# ESC_C.net
KiCad netlist of a schematic drawn in Altium Designer
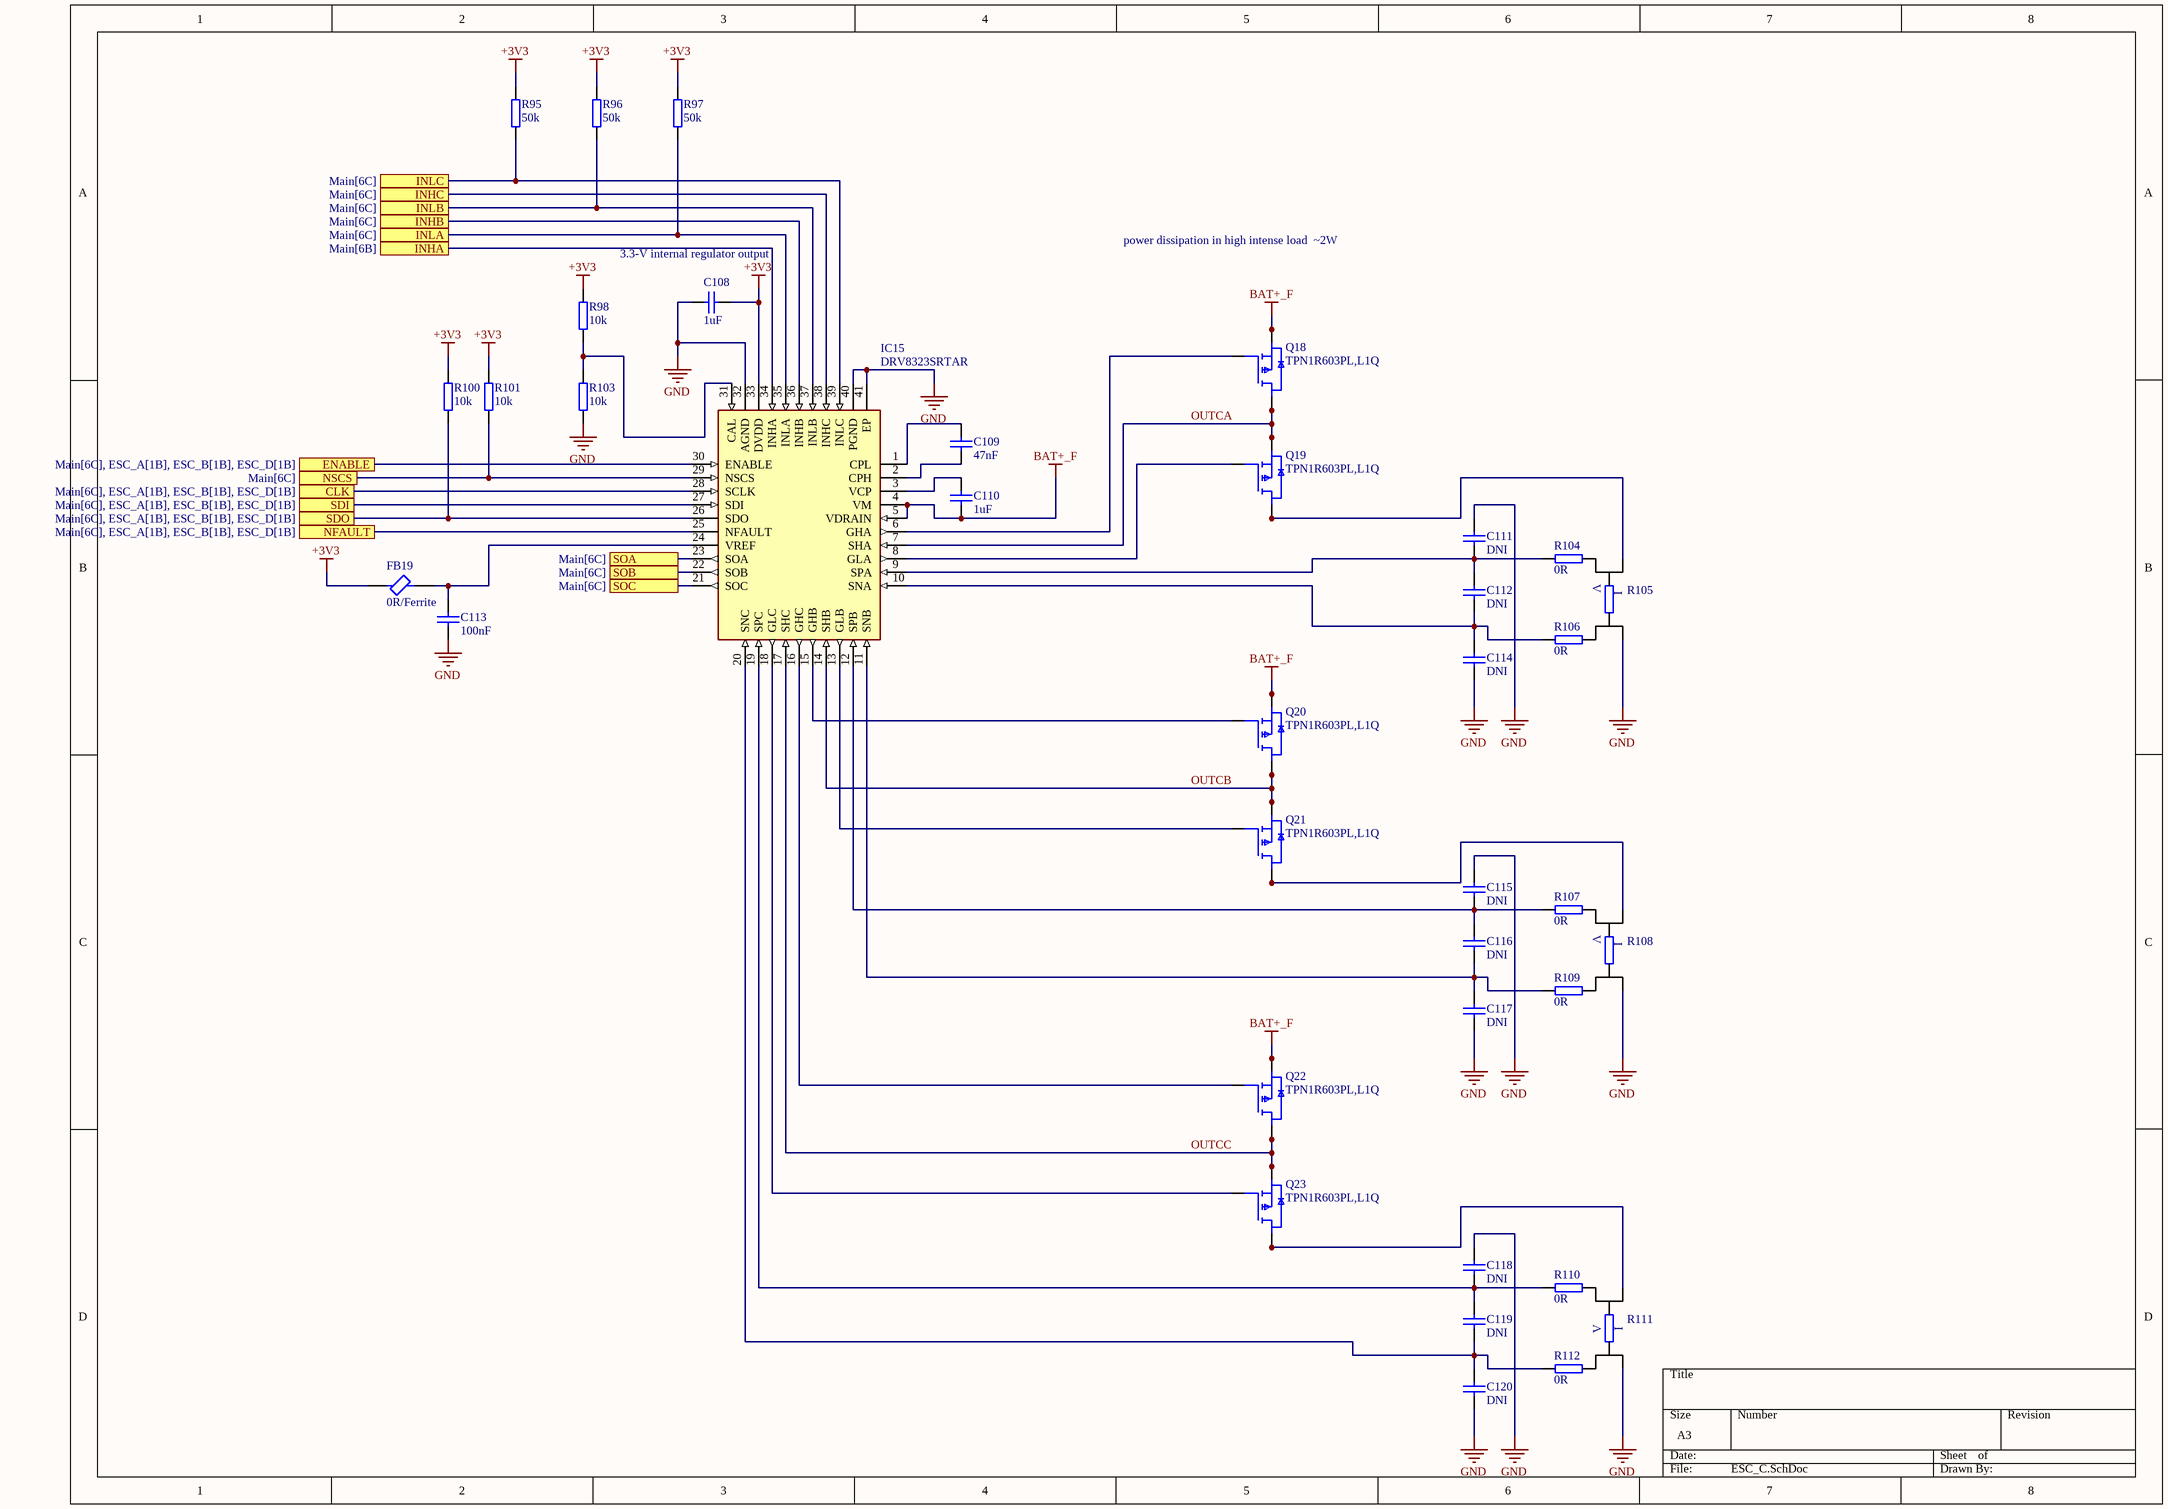
[diagram p0: ESC_C.SchDoc]

(export (version "E")
  (design (tool "Eeschema 10.0.6"))
  (components
    (comp (ref "C108")
      (value "1uF")
      (footprint "CAP0402")
      (fields (field (name "VOLTAGE") "val") (field (name "Comment") "Cap0402"))
      (libsource (lib "capacitorsSMD") (part "Cap0402"))
    )
    (comp (ref "C109")
      (value "47nF")
      (footprint "CAP0603")
      (description "50V")
      (fields (field (name "Comment") "CapSMD0603") (field (name "PUBLISHER") "Altium Limited"))
      (libsource (lib "capacitorsSMD") (part "CapSMD0603"))
    )
    (comp (ref "C110")
      (value "1uF")
      (footprint "CAP0603")
      (description "50V")
      (fields (field (name "Comment") "CapSMD0603") (field (name "PUBLISHER") "Altium Limited"))
      (libsource (lib "capacitorsSMD") (part "CapSMD0603"))
    )
    (comp (ref "C111")
      (value "DNI")
      (footprint "CAP0402")
      (fields (field (name "Comment") "Cap0402"))
      (libsource (lib "capacitorsSMD") (part "Cap0402"))
    )
    (comp (ref "C112")
      (value "DNI")
      (footprint "CAP0402")
      (fields (field (name "Comment") "Cap0402"))
      (libsource (lib "capacitorsSMD") (part "Cap0402"))
    )
    (comp (ref "C113")
      (value "100nF")
      (footprint "CAP0402")
      (fields (field (name "VOLTAGE") "6V3") (field (name "Comment") "Cap0402"))
      (libsource (lib "capacitorsSMD") (part "Cap0402"))
    )
    (comp (ref "C114")
      (value "DNI")
      (footprint "CAP0402")
      (fields (field (name "Comment") "Cap0402"))
      (libsource (lib "capacitorsSMD") (part "Cap0402"))
    )
    (comp (ref "C115")
      (value "DNI")
      (footprint "CAP0402")
      (fields (field (name "Comment") "Cap0402"))
      (libsource (lib "capacitorsSMD") (part "Cap0402"))
    )
    (comp (ref "C116")
      (value "DNI")
      (footprint "CAP0402")
      (fields (field (name "Comment") "Cap0402"))
      (libsource (lib "capacitorsSMD") (part "Cap0402"))
    )
    (comp (ref "C117")
      (value "DNI")
      (footprint "CAP0402")
      (fields (field (name "Comment") "Cap0402"))
      (libsource (lib "capacitorsSMD") (part "Cap0402"))
    )
    (comp (ref "C118")
      (value "DNI")
      (footprint "CAP0402")
      (fields (field (name "Comment") "Cap0402"))
      (libsource (lib "capacitorsSMD") (part "Cap0402"))
    )
    (comp (ref "C119")
      (value "DNI")
      (footprint "CAP0402")
      (fields (field (name "Comment") "Cap0402"))
      (libsource (lib "capacitorsSMD") (part "Cap0402"))
    )
    (comp (ref "C120")
      (value "DNI")
      (footprint "CAP0402")
      (fields (field (name "Comment") "Cap0402"))
      (libsource (lib "capacitorsSMD") (part "Cap0402"))
    )
    (comp (ref "FB19")
      (value "0R/Ferrite")
      (footprint "SamacSys:NFZ15SG152SN10B")
      (description "Ferrite Bead")
      (fields
        (field (name "MANUFACTURER_PART_NUMBER") "BLM15PE471SH1D")
        (field (name "MOUSER PART NUMBER") "81-BLM15PE471SH1D")
      )
      (libsource (lib "SamacSys") (part "BLM15PE471SH1D"))
    )
    (comp (ref "IC15")
      (value "DRV8323SRTAR")
      (footprint "SamacSys:QFN50P600X600X80-41N-D")
      (description "Integrated Circuit")
      (fields (field (name "MOUSER PART NUMBER") "595-DRV8323SRTAR"))
      (libsource (lib "*") (part "DRV8323SRTAR"))
    )
    (comp (ref "Q18")
      (value "TPN1R603PL,L1Q")
      (footprint "SamacSys:TPN1R603PLL1Q")
      (description "MOSFET (N-Channel)")
      (fields (field (name "MOUSER PART NUMBER") "757-TPN1R603PLL1Q"))
      (libsource (lib "SamacSys") (part "TPN1R603PL,L1Q"))
    )
    (comp (ref "Q19")
      (value "TPN1R603PL,L1Q")
      (footprint "SamacSys:TPN1R603PLL1Q")
      (description "MOSFET (N-Channel)")
      (fields (field (name "MOUSER PART NUMBER") "757-TPN1R603PLL1Q"))
      (libsource (lib "SamacSys") (part "TPN1R603PL,L1Q"))
    )
    (comp (ref "Q20")
      (value "TPN1R603PL,L1Q")
      (footprint "SamacSys:TPN1R603PLL1Q")
      (description "MOSFET (N-Channel)")
      (fields (field (name "MOUSER PART NUMBER") "757-TPN1R603PLL1Q"))
      (libsource (lib "SamacSys") (part "TPN1R603PL,L1Q"))
    )
    (comp (ref "Q21")
      (value "TPN1R603PL,L1Q")
      (footprint "SamacSys:TPN1R603PLL1Q")
      (description "MOSFET (N-Channel)")
      (fields (field (name "MOUSER PART NUMBER") "757-TPN1R603PLL1Q"))
      (libsource (lib "SamacSys") (part "TPN1R603PL,L1Q"))
    )
    (comp (ref "Q22")
      (value "TPN1R603PL,L1Q")
      (footprint "SamacSys:TPN1R603PLL1Q")
      (description "MOSFET (N-Channel)")
      (fields (field (name "MOUSER PART NUMBER") "757-TPN1R603PLL1Q"))
      (libsource (lib "SamacSys") (part "TPN1R603PL,L1Q"))
    )
    (comp (ref "Q23")
      (value "TPN1R603PL,L1Q")
      (footprint "SamacSys:TPN1R603PLL1Q")
      (description "MOSFET (N-Channel)")
      (fields (field (name "MOUSER PART NUMBER") "757-TPN1R603PLL1Q"))
      (libsource (lib "SamacSys") (part "TPN1R603PL,L1Q"))
    )
    (comp (ref "R95")
      (value "50k")
      (footprint "RES0402")
      (fields (field (name "Comment") "Res0402"))
      (libsource (lib "resistorSMD") (part "Res0402"))
    )
    (comp (ref "R96")
      (value "50k")
      (footprint "RES0402")
      (fields (field (name "Comment") "Res0402"))
      (libsource (lib "resistorSMD") (part "Res0402"))
    )
    (comp (ref "R97")
      (value "50k")
      (footprint "RES0402")
      (fields (field (name "Comment") "Res0402"))
      (libsource (lib "resistorSMD") (part "Res0402"))
    )
    (comp (ref "R98")
      (value "10k")
      (footprint "RES0402")
      (fields (field (name "Comment") "Res0402"))
      (libsource (lib "resistorSMD") (part "Res0402"))
    )
    (comp (ref "R100")
      (value "10k")
      (footprint "RES0402")
      (fields (field (name "Comment") "Res0402"))
      (libsource (lib "resistorSMD") (part "Res0402"))
    )
    (comp (ref "R101")
      (value "10k")
      (footprint "RES0402")
      (fields (field (name "Comment") "Res0402"))
      (libsource (lib "resistorSMD") (part "Res0402"))
    )
    (comp (ref "R103")
      (value "10k")
      (footprint "RES0402")
      (fields (field (name "Comment") "Res0402"))
      (libsource (lib "resistorSMD") (part "Res0402"))
    )
    (comp (ref "R104")
      (value "0R")
      (footprint "RES0402")
      (fields (field (name "Comment") "Res0402"))
      (libsource (lib "resistorSMD") (part "Res0402"))
    )
    (comp (ref "R105")
      (value "WSK12161L000FEA")
      (footprint "SamacSys:WSK12161L000FEA")
      (description "Resistor")
      (fields
        (field (name "MANUFACTURER_PART_NUMBER") "WSK1216L5000FEA")
        (field (name "MOUSER PART NUMBER") "71-WSK1216L5000FEA")
      )
      (libsource (lib "SamacSys") (part "WSK1216L5000FEA"))
    )
    (comp (ref "R106")
      (value "0R")
      (footprint "RES0402")
      (fields (field (name "Comment") "Res0402"))
      (libsource (lib "resistorSMD") (part "Res0402"))
    )
    (comp (ref "R107")
      (value "0R")
      (footprint "RES0402")
      (fields (field (name "Comment") "Res0402"))
      (libsource (lib "resistorSMD") (part "Res0402"))
    )
    (comp (ref "R108")
      (value "WSK12161L000FEA")
      (footprint "SamacSys:WSK12161L000FEA")
      (description "Resistor")
      (fields
        (field (name "MANUFACTURER_PART_NUMBER") "WSK1216L5000FEA")
        (field (name "MOUSER PART NUMBER") "71-WSK1216L5000FEA")
      )
      (libsource (lib "SamacSys") (part "WSK1216L5000FEA"))
    )
    (comp (ref "R109")
      (value "0R")
      (footprint "RES0402")
      (fields (field (name "Comment") "Res0402"))
      (libsource (lib "resistorSMD") (part "Res0402"))
    )
    (comp (ref "R110")
      (value "0R")
      (footprint "RES0402")
      (fields (field (name "Comment") "Res0402"))
      (libsource (lib "resistorSMD") (part "Res0402"))
    )
    (comp (ref "R111")
      (value "WSK12161L000FEA")
      (footprint "SamacSys:WSK12161L000FEA")
      (description "Resistor")
      (fields
        (field (name "MANUFACTURER_PART_NUMBER") "WSK1216L5000FEA")
        (field (name "MOUSER PART NUMBER") "71-WSK1216L5000FEA")
      )
      (libsource (lib "SamacSys") (part "WSK1216L5000FEA"))
    )
    (comp (ref "R112")
      (value "0R")
      (footprint "RES0402")
      (fields (field (name "Comment") "Res0402"))
      (libsource (lib "resistorSMD") (part "Res0402"))
    )
  )
  (nets
    (net (code "1") (name "+3V3") (class "Default")
      (node (ref "C108") (pin "2") (pinfunction "2_2") (pintype "passive"))
      (node (ref "FB19") (pin "1") (pinfunction "1_1") (pintype "passive"))
      (node (ref "IC15") (pin "33") (pinfunction "DVDD_33") (pintype "power_in"))
      (node (ref "R100") (pin "2") (pinfunction "2_2") (pintype "passive"))
      (node (ref "R101") (pin "2") (pinfunction "2_2") (pintype "passive"))
      (node (ref "R95") (pin "2") (pinfunction "2_2") (pintype "passive"))
      (node (ref "R96") (pin "2") (pinfunction "2_2") (pintype "passive"))
      (node (ref "R97") (pin "2") (pinfunction "2_2") (pintype "passive"))
      (node (ref "R98") (pin "2") (pinfunction "2_2") (pintype "passive"))
    )
    (net (code "2") (name "/CLK") (class "Default")
      (node (ref "IC15") (pin "28") (pinfunction "SCLK_28") (pintype "input"))
    )
    (net (code "3") (name "/ENABLE") (class "Default")
      (node (ref "IC15") (pin "30") (pinfunction "ENABLE_30") (pintype "input"))
    )
    (net (code "4") (name "/INHA") (class "Default")
      (node (ref "IC15") (pin "34") (pinfunction "INHA_34") (pintype "input"))
    )
    (net (code "5") (name "/INHB") (class "Default")
      (node (ref "IC15") (pin "36") (pinfunction "INHB_36") (pintype "input"))
    )
    (net (code "6") (name "/INHC") (class "Default")
      (node (ref "IC15") (pin "38") (pinfunction "INHC_38") (pintype "input"))
    )
    (net (code "7") (name "/INLA") (class "Default")
      (node (ref "IC15") (pin "35") (pinfunction "INLA_35") (pintype "input"))
      (node (ref "R97") (pin "1") (pinfunction "1_1") (pintype "passive"))
    )
    (net (code "8") (name "/INLB") (class "Default")
      (node (ref "IC15") (pin "37") (pinfunction "INLB_37") (pintype "input"))
      (node (ref "R96") (pin "1") (pinfunction "1_1") (pintype "passive"))
    )
    (net (code "9") (name "/INLC") (class "Default")
      (node (ref "IC15") (pin "39") (pinfunction "INLC_39") (pintype "input"))
      (node (ref "R95") (pin "1") (pinfunction "1_1") (pintype "passive"))
    )
    (net (code "10") (name "/NFAULT") (class "Default")
      (node (ref "IC15") (pin "25") (pinfunction "NFAULT_25") (pintype "passive"))
    )
    (net (code "11") (name "/NSCS") (class "Default")
      (node (ref "IC15") (pin "29") (pinfunction "NSCS_29") (pintype "input"))
      (node (ref "R101") (pin "1") (pinfunction "1_1") (pintype "passive"))
    )
    (net (code "12") (name "/OUTCA") (class "Default")
      (node (ref "IC15") (pin "7") (pinfunction "SHA_7") (pintype "input"))
      (node (ref "Q18") (pin "5") (pinfunction "D_1_5") (pintype "passive"))
      (node (ref "Q18") (pin "6") (pinfunction "D_2_6") (pintype "passive"))
      (node (ref "Q18") (pin "7") (pinfunction "D_3_7") (pintype "passive"))
      (node (ref "Q18") (pin "8") (pinfunction "D_4_8") (pintype "passive"))
      (node (ref "Q18") (pin "9") (pinfunction "D_4_9") (pintype "passive"))
      (node (ref "Q19") (pin "1") (pinfunction "S_1_1") (pintype "passive"))
      (node (ref "Q19") (pin "2") (pinfunction "S_2_2") (pintype "passive"))
      (node (ref "Q19") (pin "3") (pinfunction "S_3_3") (pintype "passive"))
    )
    (net (code "13") (name "/OUTCB") (class "Default")
      (node (ref "IC15") (pin "14") (pinfunction "SHB_14") (pintype "input"))
      (node (ref "Q20") (pin "5") (pinfunction "D_1_5") (pintype "passive"))
      (node (ref "Q20") (pin "6") (pinfunction "D_2_6") (pintype "passive"))
      (node (ref "Q20") (pin "7") (pinfunction "D_3_7") (pintype "passive"))
      (node (ref "Q20") (pin "8") (pinfunction "D_4_8") (pintype "passive"))
      (node (ref "Q20") (pin "9") (pinfunction "D_4_9") (pintype "passive"))
      (node (ref "Q21") (pin "1") (pinfunction "S_1_1") (pintype "passive"))
      (node (ref "Q21") (pin "2") (pinfunction "S_2_2") (pintype "passive"))
      (node (ref "Q21") (pin "3") (pinfunction "S_3_3") (pintype "passive"))
    )
    (net (code "14") (name "/OUTCC") (class "Default")
      (node (ref "IC15") (pin "17") (pinfunction "SHC_17") (pintype "input"))
      (node (ref "Q22") (pin "5") (pinfunction "D_1_5") (pintype "passive"))
      (node (ref "Q22") (pin "6") (pinfunction "D_2_6") (pintype "passive"))
      (node (ref "Q22") (pin "7") (pinfunction "D_3_7") (pintype "passive"))
      (node (ref "Q22") (pin "8") (pinfunction "D_4_8") (pintype "passive"))
      (node (ref "Q22") (pin "9") (pinfunction "D_4_9") (pintype "passive"))
      (node (ref "Q23") (pin "1") (pinfunction "S_1_1") (pintype "passive"))
      (node (ref "Q23") (pin "2") (pinfunction "S_2_2") (pintype "passive"))
      (node (ref "Q23") (pin "3") (pinfunction "S_3_3") (pintype "passive"))
    )
    (net (code "15") (name "/SDI") (class "Default")
      (node (ref "IC15") (pin "27") (pinfunction "SDI_27") (pintype "input"))
    )
    (net (code "16") (name "/SDO") (class "Default")
      (node (ref "IC15") (pin "26") (pinfunction "SDO_26") (pintype "passive"))
      (node (ref "R100") (pin "1") (pinfunction "1_1") (pintype "passive"))
    )
    (net (code "17") (name "/SOA") (class "Default")
      (node (ref "IC15") (pin "23") (pinfunction "SOA_23") (pintype "output"))
    )
    (net (code "18") (name "/SOB") (class "Default")
      (node (ref "IC15") (pin "22") (pinfunction "SOB_22") (pintype "output"))
    )
    (net (code "19") (name "/SOC") (class "Default")
      (node (ref "IC15") (pin "21") (pinfunction "SOC_21") (pintype "output"))
    )
    (net (code "20") (name "BAT+_F") (class "Default")
      (node (ref "C110") (pin "1") (pinfunction "1_1") (pintype "passive"))
      (node (ref "IC15") (pin "4") (pinfunction "VM_4") (pintype "power_in"))
      (node (ref "IC15") (pin "5") (pinfunction "VDRAIN_5") (pintype "input"))
      (node (ref "Q18") (pin "1") (pinfunction "S_1_1") (pintype "passive"))
      (node (ref "Q18") (pin "2") (pinfunction "S_2_2") (pintype "passive"))
      (node (ref "Q18") (pin "3") (pinfunction "S_3_3") (pintype "passive"))
      (node (ref "Q20") (pin "1") (pinfunction "S_1_1") (pintype "passive"))
      (node (ref "Q20") (pin "2") (pinfunction "S_2_2") (pintype "passive"))
      (node (ref "Q20") (pin "3") (pinfunction "S_3_3") (pintype "passive"))
      (node (ref "Q22") (pin "1") (pinfunction "S_1_1") (pintype "passive"))
      (node (ref "Q22") (pin "2") (pinfunction "S_2_2") (pintype "passive"))
      (node (ref "Q22") (pin "3") (pinfunction "S_3_3") (pintype "passive"))
    )
    (net (code "21") (name "GND") (class "Default")
      (node (ref "C108") (pin "1") (pinfunction "1_1") (pintype "passive"))
      (node (ref "C111") (pin "1") (pinfunction "1_1") (pintype "passive"))
      (node (ref "C113") (pin "1") (pinfunction "1_1") (pintype "passive"))
      (node (ref "C114") (pin "2") (pinfunction "2_2") (pintype "passive"))
      (node (ref "C115") (pin "1") (pinfunction "1_1") (pintype "passive"))
      (node (ref "C117") (pin "2") (pinfunction "2_2") (pintype "passive"))
      (node (ref "C118") (pin "1") (pinfunction "1_1") (pintype "passive"))
      (node (ref "C120") (pin "2") (pinfunction "2_2") (pintype "passive"))
      (node (ref "IC15") (pin "32") (pinfunction "AGND_32") (pintype "power_in"))
      (node (ref "IC15") (pin "40") (pinfunction "PGND_40") (pintype "power_in"))
      (node (ref "IC15") (pin "41") (pinfunction "EP_41") (pintype "power_in"))
      (node (ref "R103") (pin "1") (pinfunction "1_1") (pintype "passive"))
      (node (ref "R105") (pin "4") (pinfunction "4_4") (pintype "passive"))
      (node (ref "R108") (pin "4") (pinfunction "4_4") (pintype "passive"))
      (node (ref "R111") (pin "1") (pinfunction "1_1") (pintype "passive"))
    )
    (net (code "22") (name "Net-(IC15-CAL)") (class "Default")
      (node (ref "IC15") (pin "31") (pinfunction "CAL_31") (pintype "input"))
      (node (ref "R103") (pin "2") (pinfunction "2_2") (pintype "passive"))
      (node (ref "R98") (pin "1") (pinfunction "1_1") (pintype "passive"))
    )
    (net (code "23") (name "Net-(IC15-CPH)") (class "Default")
      (node (ref "C109") (pin "1") (pinfunction "1_1") (pintype "passive"))
      (node (ref "IC15") (pin "2") (pinfunction "CPH_2") (pintype "power_in"))
    )
    (net (code "24") (name "Net-(IC15-CPL)") (class "Default")
      (node (ref "C109") (pin "2") (pinfunction "2_2") (pintype "passive"))
      (node (ref "IC15") (pin "1") (pinfunction "CPL_1") (pintype "power_in"))
    )
    (net (code "25") (name "Net-(IC15-GHA)") (class "Default")
      (node (ref "IC15") (pin "6") (pinfunction "GHA_6") (pintype "output"))
      (node (ref "Q18") (pin "4") (pinfunction "G_4") (pintype "passive"))
    )
    (net (code "26") (name "Net-(IC15-GHB)") (class "Default")
      (node (ref "IC15") (pin "15") (pinfunction "GHB_15") (pintype "output"))
      (node (ref "Q20") (pin "4") (pinfunction "G_4") (pintype "passive"))
    )
    (net (code "27") (name "Net-(IC15-GHC)") (class "Default")
      (node (ref "IC15") (pin "16") (pinfunction "GHC_16") (pintype "output"))
      (node (ref "Q22") (pin "4") (pinfunction "G_4") (pintype "passive"))
    )
    (net (code "28") (name "Net-(IC15-GLA)") (class "Default")
      (node (ref "IC15") (pin "8") (pinfunction "GLA_8") (pintype "output"))
      (node (ref "Q19") (pin "4") (pinfunction "G_4") (pintype "passive"))
    )
    (net (code "29") (name "Net-(IC15-GLB)") (class "Default")
      (node (ref "IC15") (pin "13") (pinfunction "GLB_13") (pintype "output"))
      (node (ref "Q21") (pin "4") (pinfunction "G_4") (pintype "passive"))
    )
    (net (code "30") (name "Net-(IC15-GLC)") (class "Default")
      (node (ref "IC15") (pin "18") (pinfunction "GLC_18") (pintype "output"))
      (node (ref "Q23") (pin "4") (pinfunction "G_4") (pintype "passive"))
    )
    (net (code "31") (name "Net-(IC15-SNA)") (class "Default")
      (node (ref "C112") (pin "2") (pinfunction "2_2") (pintype "passive"))
      (node (ref "C114") (pin "1") (pinfunction "1_1") (pintype "passive"))
      (node (ref "IC15") (pin "10") (pinfunction "SNA_10") (pintype "input"))
      (node (ref "R106") (pin "1") (pinfunction "1_1") (pintype "passive"))
    )
    (net (code "32") (name "Net-(IC15-SNB)") (class "Default")
      (node (ref "C116") (pin "2") (pinfunction "2_2") (pintype "passive"))
      (node (ref "C117") (pin "1") (pinfunction "1_1") (pintype "passive"))
      (node (ref "IC15") (pin "11") (pinfunction "SNB_11") (pintype "input"))
      (node (ref "R109") (pin "1") (pinfunction "1_1") (pintype "passive"))
    )
    (net (code "33") (name "Net-(IC15-SNC)") (class "Default")
      (node (ref "C119") (pin "2") (pinfunction "2_2") (pintype "passive"))
      (node (ref "C120") (pin "1") (pinfunction "1_1") (pintype "passive"))
      (node (ref "IC15") (pin "20") (pinfunction "SNC_20") (pintype "input"))
      (node (ref "R112") (pin "1") (pinfunction "1_1") (pintype "passive"))
    )
    (net (code "34") (name "Net-(IC15-SPA)") (class "Default")
      (node (ref "C111") (pin "2") (pinfunction "2_2") (pintype "passive"))
      (node (ref "C112") (pin "1") (pinfunction "1_1") (pintype "passive"))
      (node (ref "IC15") (pin "9") (pinfunction "SPA_9") (pintype "input"))
      (node (ref "R104") (pin "1") (pinfunction "1_1") (pintype "passive"))
    )
    (net (code "35") (name "Net-(IC15-SPB)") (class "Default")
      (node (ref "C115") (pin "2") (pinfunction "2_2") (pintype "passive"))
      (node (ref "C116") (pin "1") (pinfunction "1_1") (pintype "passive"))
      (node (ref "IC15") (pin "12") (pinfunction "SPB_12") (pintype "input"))
      (node (ref "R107") (pin "1") (pinfunction "1_1") (pintype "passive"))
    )
    (net (code "36") (name "Net-(IC15-SPC)") (class "Default")
      (node (ref "C118") (pin "2") (pinfunction "2_2") (pintype "passive"))
      (node (ref "C119") (pin "1") (pinfunction "1_1") (pintype "passive"))
      (node (ref "IC15") (pin "19") (pinfunction "SPC_19") (pintype "input"))
      (node (ref "R110") (pin "1") (pinfunction "1_1") (pintype "passive"))
    )
    (net (code "37") (name "Net-(IC15-VCP)") (class "Default")
      (node (ref "C110") (pin "2") (pinfunction "2_2") (pintype "passive"))
      (node (ref "IC15") (pin "3") (pinfunction "VCP_3") (pintype "power_in"))
    )
    (net (code "38") (name "Net-(IC15-VREF)") (class "Default")
      (node (ref "C113") (pin "2") (pinfunction "2_2") (pintype "passive"))
      (node (ref "FB19") (pin "2") (pinfunction "2_2") (pintype "passive"))
      (node (ref "IC15") (pin "24") (pinfunction "VREF_24") (pintype "power_in"))
    )
    (net (code "39") (name "Net-(Q19-D_1)") (class "Default")
      (node (ref "Q19") (pin "5") (pinfunction "D_1_5") (pintype "passive"))
      (node (ref "Q19") (pin "6") (pinfunction "D_2_6") (pintype "passive"))
      (node (ref "Q19") (pin "7") (pinfunction "D_3_7") (pintype "passive"))
      (node (ref "Q19") (pin "8") (pinfunction "D_4_8") (pintype "passive"))
      (node (ref "Q19") (pin "9") (pinfunction "D_4_9") (pintype "passive"))
      (node (ref "R105") (pin "1") (pinfunction "1_1") (pintype "passive"))
    )
    (net (code "40") (name "Net-(Q21-D_1)") (class "Default")
      (node (ref "Q21") (pin "5") (pinfunction "D_1_5") (pintype "passive"))
      (node (ref "Q21") (pin "6") (pinfunction "D_2_6") (pintype "passive"))
      (node (ref "Q21") (pin "7") (pinfunction "D_3_7") (pintype "passive"))
      (node (ref "Q21") (pin "8") (pinfunction "D_4_8") (pintype "passive"))
      (node (ref "Q21") (pin "9") (pinfunction "D_4_9") (pintype "passive"))
      (node (ref "R108") (pin "1") (pinfunction "1_1") (pintype "passive"))
    )
    (net (code "41") (name "Net-(Q23-D_1)") (class "Default")
      (node (ref "Q23") (pin "5") (pinfunction "D_1_5") (pintype "passive"))
      (node (ref "Q23") (pin "6") (pinfunction "D_2_6") (pintype "passive"))
      (node (ref "Q23") (pin "7") (pinfunction "D_3_7") (pintype "passive"))
      (node (ref "Q23") (pin "8") (pinfunction "D_4_8") (pintype "passive"))
      (node (ref "Q23") (pin "9") (pinfunction "D_4_9") (pintype "passive"))
      (node (ref "R111") (pin "4") (pinfunction "4_4") (pintype "passive"))
    )
    (net (code "42") (name "Net-(R104-Pad2)") (class "Default")
      (node (ref "R104") (pin "2") (pinfunction "2_2") (pintype "passive"))
      (node (ref "R105") (pin "2") (pinfunction "2_2") (pintype "passive"))
    )
    (net (code "43") (name "Net-(R105-Pad3)") (class "Default")
      (node (ref "R105") (pin "3") (pinfunction "3_3") (pintype "passive"))
      (node (ref "R106") (pin "2") (pinfunction "2_2") (pintype "passive"))
    )
    (net (code "44") (name "Net-(R107-Pad2)") (class "Default")
      (node (ref "R107") (pin "2") (pinfunction "2_2") (pintype "passive"))
      (node (ref "R108") (pin "2") (pinfunction "2_2") (pintype "passive"))
    )
    (net (code "45") (name "Net-(R108-Pad3)") (class "Default")
      (node (ref "R108") (pin "3") (pinfunction "3_3") (pintype "passive"))
      (node (ref "R109") (pin "2") (pinfunction "2_2") (pintype "passive"))
    )
    (net (code "46") (name "Net-(R110-Pad2)") (class "Default")
      (node (ref "R110") (pin "2") (pinfunction "2_2") (pintype "passive"))
      (node (ref "R111") (pin "3") (pinfunction "3_3") (pintype "passive"))
    )
    (net (code "47") (name "Net-(R111-Pad2)") (class "Default")
      (node (ref "R111") (pin "2") (pinfunction "2_2") (pintype "passive"))
      (node (ref "R112") (pin "2") (pinfunction "2_2") (pintype "passive"))
    )
  )
)
